# openWall_onBoardPCB.net
KiCad netlist of a schematic drawn in EAGLE
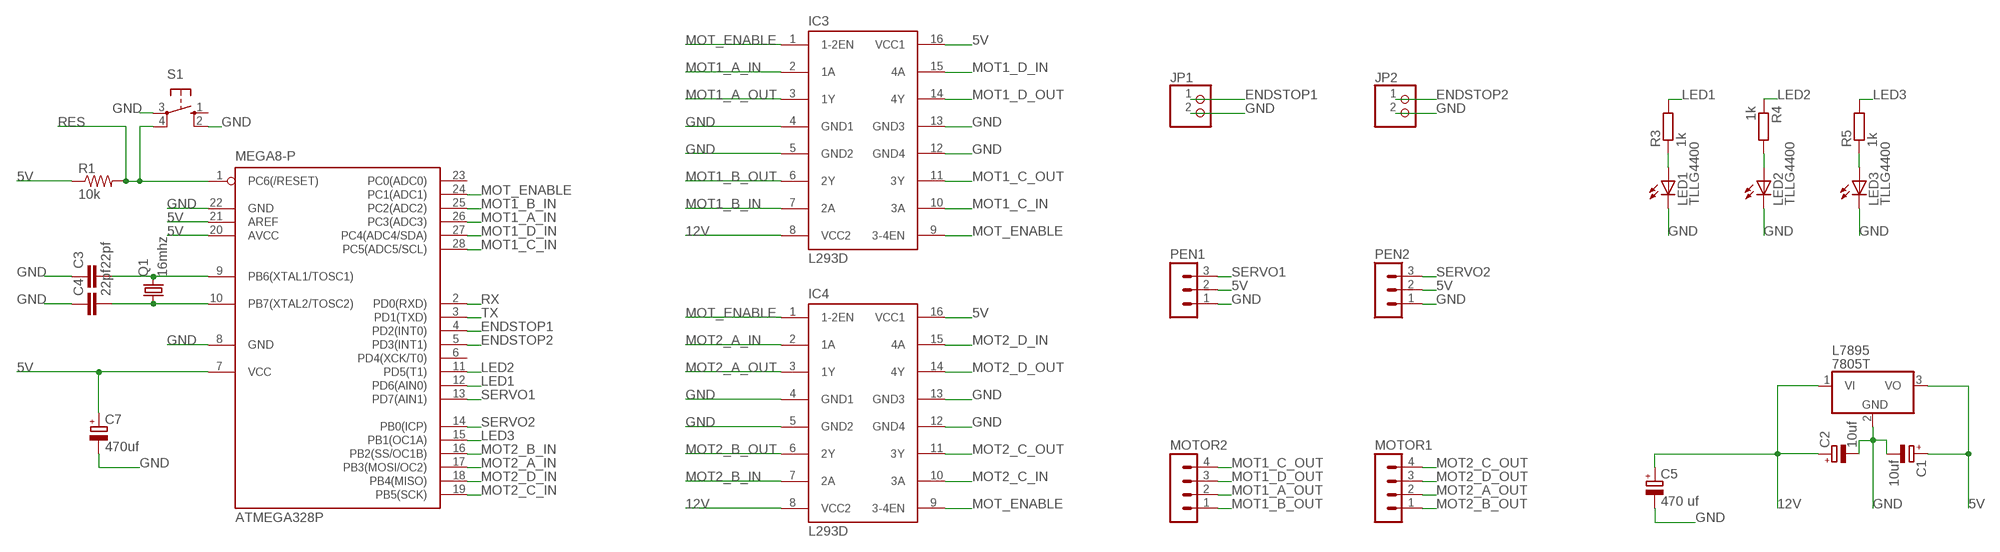
[diagram p0: schematic, sheet 1, part 1 of 2]
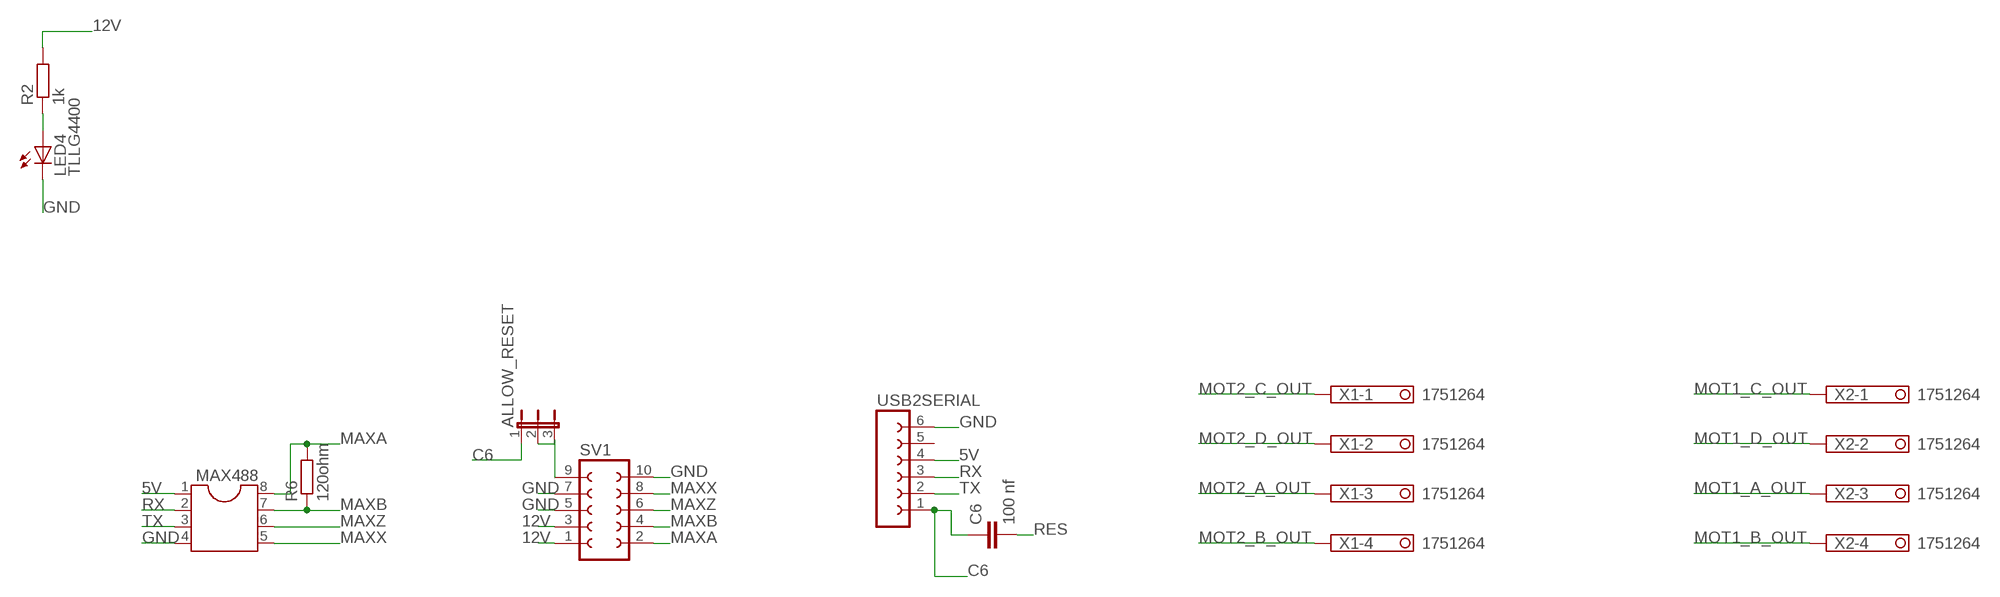
[diagram p1: schematic, sheet 1, part 2 of 2]

(export (version "E")
  (design (tool "Eeschema 10.0.6"))
  (components
    (comp (ref "ALLOW_RESET")
      (value "JP2E")
      (footprint "eagle-import:JP2")
      (libsource (lib "eagle-import") (part "JP2E"))
    )
    (comp (ref "ATMEGA328P")
      (value "MEGA8-P")
      (footprint "eagle-import:DIL28-3")
      (libsource (lib "eagle-import") (part "MEGA8-P"))
    )
    (comp (ref "C1")
      (value "10uf")
      (footprint "eagle-import:E2,5-6")
      (libsource (lib "eagle-import") (part "CPOL-EUE2.5-6"))
    )
    (comp (ref "C2")
      (value "10uf")
      (footprint "eagle-import:E2,5-6")
      (libsource (lib "eagle-import") (part "CPOL-EUE2.5-6"))
    )
    (comp (ref "C3")
      (value "22pf")
      (footprint "eagle-import:C025-030X050")
      (libsource (lib "eagle-import") (part "C-EU025-030X050"))
    )
    (comp (ref "C4")
      (value "22pf")
      (footprint "eagle-import:C025-030X050")
      (libsource (lib "eagle-import") (part "C-EU025-030X050"))
    )
    (comp (ref "C5")
      (value "470 uf")
      (footprint "eagle-import:E5-6")
      (libsource (lib "eagle-import") (part "CPOL-EUE5-6"))
    )
    (comp (ref "C6")
      (value "100 nf")
      (footprint "eagle-import:C050-024X044")
      (libsource (lib "eagle-import") (part "C-EU050-024X044"))
    )
    (comp (ref "C7")
      (value "470uf")
      (footprint "eagle-import:E5-6")
      (libsource (lib "eagle-import") (part "CPOL-EUE5-6"))
    )
    (comp (ref "IC3")
      (value "L293D")
      (footprint "eagle-import:DIL16")
      (libsource (lib "eagle-import") (part "L293D"))
    )
    (comp (ref "IC4")
      (value "L293D")
      (footprint "eagle-import:DIL16")
      (libsource (lib "eagle-import") (part "L293D"))
    )
    (comp (ref "JP1")
      (value "PINHD-1X2")
      (footprint "eagle-import:1X02")
      (libsource (lib "eagle-import") (part "PINHD-1X2"))
    )
    (comp (ref "JP2")
      (value "PINHD-1X2")
      (footprint "eagle-import:1X02")
      (libsource (lib "eagle-import") (part "PINHD-1X2"))
    )
    (comp (ref "L7895")
      (value "7805T")
      (footprint "eagle-import:TO220H")
      (libsource (lib "eagle-import") (part "78T05"))
    )
    (comp (ref "LED1")
      (value "TLLG4400")
      (footprint "eagle-import:LED3MM")
      (fields (field (name "MF") "VISHAY SEMICONDUCTOR"))
      (libsource (lib "eagle-import") (part "TLLG4400"))
    )
    (comp (ref "LED2")
      (value "TLLG4400")
      (footprint "eagle-import:LED3MM")
      (fields (field (name "MF") "VISHAY SEMICONDUCTOR"))
      (libsource (lib "eagle-import") (part "TLLG4400"))
    )
    (comp (ref "LED3")
      (value "TLLG4400")
      (footprint "eagle-import:LED3MM")
      (fields (field (name "MF") "VISHAY SEMICONDUCTOR"))
      (libsource (lib "eagle-import") (part "TLLG4400"))
    )
    (comp (ref "LED4")
      (value "TLLG4400")
      (footprint "eagle-import:LED3MM")
      (fields (field (name "MF") "VISHAY SEMICONDUCTOR"))
      (libsource (lib "eagle-import") (part "TLLG4400"))
    )
    (comp (ref "MAX488")
      (value "DIL8")
      (footprint "eagle-import:DIL08")
      (libsource (lib "eagle-import") (part "DIL8"))
    )
    (comp (ref "MOTOR1")
      (value "MA04-1")
      (footprint "eagle-import:MA04-1")
      (libsource (lib "eagle-import") (part "MA04-1"))
    )
    (comp (ref "MOTOR2")
      (value "MA04-1")
      (footprint "eagle-import:MA04-1")
      (libsource (lib "eagle-import") (part "MA04-1"))
    )
    (comp (ref "PEN1")
      (value "MA03-1")
      (footprint "eagle-import:MA03-1")
      (libsource (lib "eagle-import") (part "MA03-1"))
    )
    (comp (ref "PEN2")
      (value "MA03-1")
      (footprint "eagle-import:MA03-1")
      (libsource (lib "eagle-import") (part "MA03-1"))
    )
    (comp (ref "Q1")
      (value "16mhz")
      (footprint "eagle-import:HC49_S")
      (libsource (lib "eagle-import") (part "CRYSTALHC49S"))
    )
    (comp (ref "R1")
      (value "10k")
      (footprint "eagle-import:0207_7")
      (libsource (lib "eagle-import") (part "R-US_0207/7"))
    )
    (comp (ref "R2")
      (value "1k")
      (footprint "eagle-import:0207_7")
      (libsource (lib "eagle-import") (part "resistor_R-EU_0207/7"))
    )
    (comp (ref "R3")
      (value "1k")
      (footprint "eagle-import:0309V")
      (libsource (lib "eagle-import") (part "R-EU_0309/V"))
    )
    (comp (ref "R4")
      (value "1k")
      (footprint "eagle-import:0309V")
      (libsource (lib "eagle-import") (part "R-EU_0309/V"))
    )
    (comp (ref "R5")
      (value "1k")
      (footprint "eagle-import:0309V")
      (libsource (lib "eagle-import") (part "R-EU_0309/V"))
    )
    (comp (ref "R6")
      (value "120ohm")
      (footprint "eagle-import:0207_7")
      (libsource (lib "eagle-import") (part "R-EU_0207/7"))
    )
    (comp (ref "S1")
      (value "10-XX")
      (footprint "eagle-import:B3F-10XX")
      (fields (field (name "MPN") "B3F-1000"))
      (libsource (lib "eagle-import") (part "10-XX"))
    )
    (comp (ref "SV1")
      (value "FE05-2")
      (footprint "eagle-import:FE05-2")
      (libsource (lib "eagle-import") (part "FE05-2"))
    )
    (comp (ref "USB2SERIAL")
      (value "FE06-1")
      (footprint "eagle-import:FE06")
      (libsource (lib "eagle-import") (part "FE06-1"))
    )
    (comp (ref "X1")
      (value "1751264")
      (footprint "eagle-import:1751264")
      (libsource (lib "eagle-import") (part "1751264"))
    )
    (comp (ref "X2")
      (value "1751264")
      (footprint "eagle-import:1751264")
      (libsource (lib "eagle-import") (part "1751264"))
    )
  )
  (nets
    (net (code "1") (name "/5V") (class "Default")
      (node (ref "ATMEGA328P") (pin "20") (pinfunction "AVCC_20") (pintype "power_in"))
      (node (ref "ATMEGA328P") (pin "21") (pinfunction "AREF_21") (pintype "passive"))
      (node (ref "ATMEGA328P") (pin "7") (pinfunction "VCC_7") (pintype "power_in"))
      (node (ref "C1") (pin "+") (pinfunction "+_+") (pintype "passive"))
      (node (ref "C7") (pin "+") (pinfunction "+_+") (pintype "passive"))
      (node (ref "IC3") (pin "16") (pinfunction "VCC1_16") (pintype "power_in"))
      (node (ref "IC4") (pin "16") (pinfunction "VCC1_16") (pintype "power_in"))
      (node (ref "L7895") (pin "3") (pinfunction "VO_3") (pintype "passive"))
      (node (ref "MAX488") (pin "1") (pinfunction "1_1") (pintype "passive"))
      (node (ref "PEN1") (pin "2") (pinfunction "2_2") (pintype "passive"))
      (node (ref "PEN2") (pin "2") (pinfunction "2_2") (pintype "passive"))
      (node (ref "R1") (pin "1") (pinfunction "1_1") (pintype "passive"))
      (node (ref "USB2SERIAL") (pin "4") (pinfunction "4_4") (pintype "passive"))
    )
    (net (code "2") (name "/12V") (class "Default")
      (node (ref "C2") (pin "+") (pinfunction "+_+") (pintype "passive"))
      (node (ref "C5") (pin "+") (pinfunction "+_+") (pintype "passive"))
      (node (ref "IC3") (pin "8") (pinfunction "VCC2_8") (pintype "power_in"))
      (node (ref "IC4") (pin "8") (pinfunction "VCC2_8") (pintype "power_in"))
      (node (ref "L7895") (pin "1") (pinfunction "VI_1") (pintype "input"))
      (node (ref "R2") (pin "2") (pinfunction "2_2") (pintype "passive"))
      (node (ref "SV1") (pin "1") (pinfunction "1_1") (pintype "passive"))
      (node (ref "SV1") (pin "3") (pinfunction "3_3") (pintype "passive"))
    )
    (net (code "3") (name "/C6") (class "Default")
      (node (ref "ALLOW_RESET") (pin "1") (pinfunction "1_1") (pintype "passive"))
      (node (ref "C6") (pin "1") (pinfunction "1_1") (pintype "passive"))
      (node (ref "USB2SERIAL") (pin "1") (pinfunction "1_1") (pintype "passive"))
    )
    (net (code "4") (name "/ENDSTOP1") (class "Default")
      (node (ref "ATMEGA328P") (pin "4") (pinfunction "PD2(INT0)_4") (pintype "bidirectional"))
      (node (ref "JP1") (pin "1") (pinfunction "1_1") (pintype "passive"))
    )
    (net (code "5") (name "/ENDSTOP2") (class "Default")
      (node (ref "ATMEGA328P") (pin "5") (pinfunction "PD3(INT1)_5") (pintype "bidirectional"))
      (node (ref "JP2") (pin "1") (pinfunction "1_1") (pintype "passive"))
    )
    (net (code "6") (name "/GND") (class "Default")
      (node (ref "ATMEGA328P") (pin "22") (pinfunction "GND_22") (pintype "power_in"))
      (node (ref "ATMEGA328P") (pin "8") (pinfunction "GND_8") (pintype "power_in"))
      (node (ref "C1") (pin "-") (pinfunction "-_-") (pintype "passive"))
      (node (ref "C2") (pin "-") (pinfunction "-_-") (pintype "passive"))
      (node (ref "C3") (pin "1") (pinfunction "1_1") (pintype "passive"))
      (node (ref "C4") (pin "1") (pinfunction "1_1") (pintype "passive"))
      (node (ref "C5") (pin "-") (pinfunction "-_-") (pintype "passive"))
      (node (ref "C7") (pin "-") (pinfunction "-_-") (pintype "passive"))
      (node (ref "IC3") (pin "12") (pinfunction "GND4_12") (pintype "power_in"))
      (node (ref "IC3") (pin "13") (pinfunction "GND3_13") (pintype "power_in"))
      (node (ref "IC3") (pin "4") (pinfunction "GND1_4") (pintype "power_in"))
      (node (ref "IC3") (pin "5") (pinfunction "GND2_5") (pintype "power_in"))
      (node (ref "IC4") (pin "12") (pinfunction "GND4_12") (pintype "power_in"))
      (node (ref "IC4") (pin "13") (pinfunction "GND3_13") (pintype "power_in"))
      (node (ref "IC4") (pin "4") (pinfunction "GND1_4") (pintype "power_in"))
      (node (ref "IC4") (pin "5") (pinfunction "GND2_5") (pintype "power_in"))
      (node (ref "JP1") (pin "2") (pinfunction "2_2") (pintype "passive"))
      (node (ref "JP2") (pin "2") (pinfunction "2_2") (pintype "passive"))
      (node (ref "L7895") (pin "2") (pinfunction "GND_2") (pintype "passive"))
      (node (ref "LED1") (pin "K") (pinfunction "C_K") (pintype "passive"))
      (node (ref "LED2") (pin "K") (pinfunction "C_K") (pintype "passive"))
      (node (ref "LED3") (pin "K") (pinfunction "C_K") (pintype "passive"))
      (node (ref "LED4") (pin "K") (pinfunction "C_K") (pintype "passive"))
      (node (ref "MAX488") (pin "4") (pinfunction "4_4") (pintype "passive"))
      (node (ref "PEN1") (pin "1") (pinfunction "1_1") (pintype "passive"))
      (node (ref "PEN2") (pin "1") (pinfunction "1_1") (pintype "passive"))
      (node (ref "S1") (pin "2") (pinfunction "S1_2") (pintype "passive"))
      (node (ref "S1") (pin "3") (pinfunction "P_3") (pintype "passive"))
      (node (ref "SV1") (pin "10") (pinfunction "10_10") (pintype "passive"))
      (node (ref "SV1") (pin "5") (pinfunction "5_5") (pintype "passive"))
      (node (ref "SV1") (pin "7") (pinfunction "7_7") (pintype "passive"))
      (node (ref "USB2SERIAL") (pin "6") (pinfunction "6_6") (pintype "passive"))
    )
    (net (code "7") (name "/LED1") (class "Default")
      (node (ref "ATMEGA328P") (pin "12") (pinfunction "PD6(AIN0)_12") (pintype "bidirectional"))
      (node (ref "R3") (pin "2") (pinfunction "2_2") (pintype "passive"))
    )
    (net (code "8") (name "/LED2") (class "Default")
      (node (ref "ATMEGA328P") (pin "11") (pinfunction "PD5(T1)_11") (pintype "bidirectional"))
      (node (ref "R4") (pin "1") (pinfunction "1_1") (pintype "passive"))
    )
    (net (code "9") (name "/LED3") (class "Default")
      (node (ref "ATMEGA328P") (pin "15") (pinfunction "PB1(OC1A)_15") (pintype "bidirectional"))
      (node (ref "R5") (pin "2") (pinfunction "2_2") (pintype "passive"))
    )
    (net (code "10") (name "/MAXA") (class "Default")
      (node (ref "MAX488") (pin "8") (pinfunction "8_8") (pintype "passive"))
      (node (ref "R6") (pin "2") (pinfunction "2_2") (pintype "passive"))
      (node (ref "SV1") (pin "2") (pinfunction "2_2") (pintype "passive"))
    )
    (net (code "11") (name "/MAXB") (class "Default")
      (node (ref "MAX488") (pin "7") (pinfunction "7_7") (pintype "passive"))
      (node (ref "R6") (pin "1") (pinfunction "1_1") (pintype "passive"))
      (node (ref "SV1") (pin "4") (pinfunction "4_4") (pintype "passive"))
    )
    (net (code "12") (name "/MAXX") (class "Default")
      (node (ref "MAX488") (pin "5") (pinfunction "5_5") (pintype "passive"))
      (node (ref "SV1") (pin "8") (pinfunction "8_8") (pintype "passive"))
    )
    (net (code "13") (name "/MAXZ") (class "Default")
      (node (ref "MAX488") (pin "6") (pinfunction "6_6") (pintype "passive"))
      (node (ref "SV1") (pin "6") (pinfunction "6_6") (pintype "passive"))
    )
    (net (code "14") (name "/MOT1_A_IN") (class "Default")
      (node (ref "ATMEGA328P") (pin "26") (pinfunction "PC3(ADC3)_26") (pintype "bidirectional"))
      (node (ref "IC3") (pin "2") (pinfunction "1A_2") (pintype "input"))
    )
    (net (code "15") (name "/MOT1_A_OUT") (class "Default")
      (node (ref "IC3") (pin "3") (pinfunction "1Y_3") (pintype "output"))
      (node (ref "MOTOR2") (pin "2") (pinfunction "2_2") (pintype "passive"))
      (node (ref "X2") (pin "3") (pinfunction "K_3") (pintype "passive"))
    )
    (net (code "16") (name "/MOT1_B_IN") (class "Default")
      (node (ref "ATMEGA328P") (pin "25") (pinfunction "PC2(ADC2)_25") (pintype "bidirectional"))
      (node (ref "IC3") (pin "7") (pinfunction "2A_7") (pintype "input"))
    )
    (net (code "17") (name "/MOT1_B_OUT") (class "Default")
      (node (ref "IC3") (pin "6") (pinfunction "2Y_6") (pintype "output"))
      (node (ref "MOTOR2") (pin "1") (pinfunction "1_1") (pintype "passive"))
      (node (ref "X2") (pin "4") (pinfunction "K_4") (pintype "passive"))
    )
    (net (code "18") (name "/MOT1_C_IN") (class "Default")
      (node (ref "ATMEGA328P") (pin "28") (pinfunction "PC5(ADC5/SCL)_28") (pintype "bidirectional"))
      (node (ref "IC3") (pin "10") (pinfunction "3A_10") (pintype "input"))
    )
    (net (code "19") (name "/MOT1_C_OUT") (class "Default")
      (node (ref "IC3") (pin "11") (pinfunction "3Y_11") (pintype "output"))
      (node (ref "MOTOR2") (pin "4") (pinfunction "4_4") (pintype "passive"))
      (node (ref "X2") (pin "1") (pinfunction "K_1") (pintype "passive"))
    )
    (net (code "20") (name "/MOT1_D_IN") (class "Default")
      (node (ref "ATMEGA328P") (pin "27") (pinfunction "PC4(ADC4/SDA)_27") (pintype "bidirectional"))
      (node (ref "IC3") (pin "15") (pinfunction "4A_15") (pintype "input"))
    )
    (net (code "21") (name "/MOT1_D_OUT") (class "Default")
      (node (ref "IC3") (pin "14") (pinfunction "4Y_14") (pintype "output"))
      (node (ref "MOTOR2") (pin "3") (pinfunction "3_3") (pintype "passive"))
      (node (ref "X2") (pin "2") (pinfunction "K_2") (pintype "passive"))
    )
    (net (code "22") (name "/MOT2_A_IN") (class "Default")
      (node (ref "ATMEGA328P") (pin "17") (pinfunction "PB3(MOSI/OC2)_17") (pintype "bidirectional"))
      (node (ref "IC4") (pin "2") (pinfunction "1A_2") (pintype "input"))
    )
    (net (code "23") (name "/MOT2_A_OUT") (class "Default")
      (node (ref "IC4") (pin "3") (pinfunction "1Y_3") (pintype "output"))
      (node (ref "MOTOR1") (pin "2") (pinfunction "2_2") (pintype "passive"))
      (node (ref "X1") (pin "3") (pinfunction "K_3") (pintype "passive"))
    )
    (net (code "24") (name "/MOT2_B_IN") (class "Default")
      (node (ref "ATMEGA328P") (pin "16") (pinfunction "PB2(SS/OC1B)_16") (pintype "bidirectional"))
      (node (ref "IC4") (pin "7") (pinfunction "2A_7") (pintype "input"))
    )
    (net (code "25") (name "/MOT2_B_OUT") (class "Default")
      (node (ref "IC4") (pin "6") (pinfunction "2Y_6") (pintype "output"))
      (node (ref "MOTOR1") (pin "1") (pinfunction "1_1") (pintype "passive"))
      (node (ref "X1") (pin "4") (pinfunction "K_4") (pintype "passive"))
    )
    (net (code "26") (name "/MOT2_C_IN") (class "Default")
      (node (ref "ATMEGA328P") (pin "19") (pinfunction "PB5(SCK)_19") (pintype "bidirectional"))
      (node (ref "IC4") (pin "10") (pinfunction "3A_10") (pintype "input"))
    )
    (net (code "27") (name "/MOT2_C_OUT") (class "Default")
      (node (ref "IC4") (pin "11") (pinfunction "3Y_11") (pintype "output"))
      (node (ref "MOTOR1") (pin "4") (pinfunction "4_4") (pintype "passive"))
      (node (ref "X1") (pin "1") (pinfunction "K_1") (pintype "passive"))
    )
    (net (code "28") (name "/MOT2_D_IN") (class "Default")
      (node (ref "ATMEGA328P") (pin "18") (pinfunction "PB4(MISO)_18") (pintype "bidirectional"))
      (node (ref "IC4") (pin "15") (pinfunction "4A_15") (pintype "input"))
    )
    (net (code "29") (name "/MOT2_D_OUT") (class "Default")
      (node (ref "IC4") (pin "14") (pinfunction "4Y_14") (pintype "output"))
      (node (ref "MOTOR1") (pin "3") (pinfunction "3_3") (pintype "passive"))
      (node (ref "X1") (pin "2") (pinfunction "K_2") (pintype "passive"))
    )
    (net (code "30") (name "/MOT_ENABLE") (class "Default")
      (node (ref "ATMEGA328P") (pin "24") (pinfunction "PC1(ADC1)_24") (pintype "bidirectional"))
      (node (ref "IC3") (pin "1") (pinfunction "1-2EN_1") (pintype "input"))
      (node (ref "IC3") (pin "9") (pinfunction "3-4EN_9") (pintype "input"))
      (node (ref "IC4") (pin "1") (pinfunction "1-2EN_1") (pintype "input"))
      (node (ref "IC4") (pin "9") (pinfunction "3-4EN_9") (pintype "input"))
    )
    (net (code "31") (name "/RES") (class "Default")
      (node (ref "ATMEGA328P") (pin "1") (pinfunction "PC6(/RESET)_1") (pintype "bidirectional"))
      (node (ref "C6") (pin "2") (pinfunction "2_2") (pintype "passive"))
      (node (ref "R1") (pin "2") (pinfunction "2_2") (pintype "passive"))
      (node (ref "S1") (pin "4") (pinfunction "P1_4") (pintype "passive"))
    )
    (net (code "32") (name "/RX") (class "Default")
      (node (ref "ATMEGA328P") (pin "2") (pinfunction "PD0(RXD)_2") (pintype "bidirectional"))
      (node (ref "MAX488") (pin "2") (pinfunction "2_2") (pintype "passive"))
      (node (ref "USB2SERIAL") (pin "3") (pinfunction "3_3") (pintype "passive"))
    )
    (net (code "33") (name "/SERVO1") (class "Default")
      (node (ref "ATMEGA328P") (pin "13") (pinfunction "PD7(AIN1)_13") (pintype "bidirectional"))
      (node (ref "PEN1") (pin "3") (pinfunction "3_3") (pintype "passive"))
    )
    (net (code "34") (name "/SERVO2") (class "Default")
      (node (ref "ATMEGA328P") (pin "14") (pinfunction "PB0(ICP)_14") (pintype "bidirectional"))
      (node (ref "PEN2") (pin "3") (pinfunction "3_3") (pintype "passive"))
    )
    (net (code "35") (name "/TX") (class "Default")
      (node (ref "ATMEGA328P") (pin "3") (pinfunction "PD1(TXD)_3") (pintype "bidirectional"))
      (node (ref "MAX488") (pin "3") (pinfunction "3_3") (pintype "passive"))
      (node (ref "USB2SERIAL") (pin "2") (pinfunction "2_2") (pintype "passive"))
    )
    (net (code "36") (name "Net-(ALLOW_RESET-Pad2)") (class "Default")
      (node (ref "ALLOW_RESET") (pin "2") (pinfunction "2_2") (pintype "passive"))
      (node (ref "ALLOW_RESET") (pin "3") (pinfunction "3_3") (pintype "passive"))
    )
    (net (code "37") (name "Net-(ATMEGA328P-PB6(XTAL1{slash}TOSC1))") (class "Default")
      (node (ref "ATMEGA328P") (pin "9") (pinfunction "PB6(XTAL1/TOSC1)_9") (pintype "bidirectional"))
      (node (ref "C3") (pin "2") (pinfunction "2_2") (pintype "passive"))
      (node (ref "Q1") (pin "2") (pinfunction "2_2") (pintype "passive"))
    )
    (net (code "38") (name "Net-(ATMEGA328P-PB7(XTAL2{slash}TOSC2))") (class "Default")
      (node (ref "ATMEGA328P") (pin "10") (pinfunction "PB7(XTAL2/TOSC2)_10") (pintype "bidirectional"))
      (node (ref "C4") (pin "2") (pinfunction "2_2") (pintype "passive"))
      (node (ref "Q1") (pin "1") (pinfunction "1_1") (pintype "passive"))
    )
    (net (code "39") (name "Net-(LED1-PadA)") (class "Default")
      (node (ref "LED1") (pin "A") (pinfunction "A_A") (pintype "passive"))
      (node (ref "R3") (pin "1") (pinfunction "1_1") (pintype "passive"))
    )
    (net (code "40") (name "Net-(LED2-PadA)") (class "Default")
      (node (ref "LED2") (pin "A") (pinfunction "A_A") (pintype "passive"))
      (node (ref "R4") (pin "2") (pinfunction "2_2") (pintype "passive"))
    )
    (net (code "41") (name "Net-(LED3-PadA)") (class "Default")
      (node (ref "LED3") (pin "A") (pinfunction "A_A") (pintype "passive"))
      (node (ref "R5") (pin "1") (pinfunction "1_1") (pintype "passive"))
    )
    (net (code "42") (name "Net-(LED4-PadA)") (class "Default")
      (node (ref "LED4") (pin "A") (pinfunction "A_A") (pintype "passive"))
      (node (ref "R2") (pin "1") (pinfunction "1_1") (pintype "passive"))
    )
    (net (code "43") (name "unconnected-(ATMEGA328P-PC0(ADC0)-Pad23)") (class "Default")
      (node (ref "ATMEGA328P") (pin "23") (pinfunction "PC0(ADC0)_23") (pintype "bidirectional"))
    )
    (net (code "44") (name "unconnected-(ATMEGA328P-PD4(XCK{slash}T0)-Pad6)") (class "Default")
      (node (ref "ATMEGA328P") (pin "6") (pinfunction "PD4(XCK/T0)_6") (pintype "bidirectional"))
    )
    (net (code "45") (name "unconnected-(S1-S-Pad1)") (class "Default")
      (node (ref "S1") (pin "1") (pinfunction "S_1") (pintype "passive"))
    )
    (net (code "46") (name "unconnected-(SV1-Pad9)") (class "Default")
      (node (ref "SV1") (pin "9") (pinfunction "9_9") (pintype "passive"))
    )
    (net (code "47") (name "unconnected-(USB2SERIAL-Pad5)") (class "Default")
      (node (ref "USB2SERIAL") (pin "5") (pinfunction "5_5") (pintype "passive"))
    )
  )
)
